# Projeto_Lora.net
KiCad netlist of a schematic drawn in EAGLE
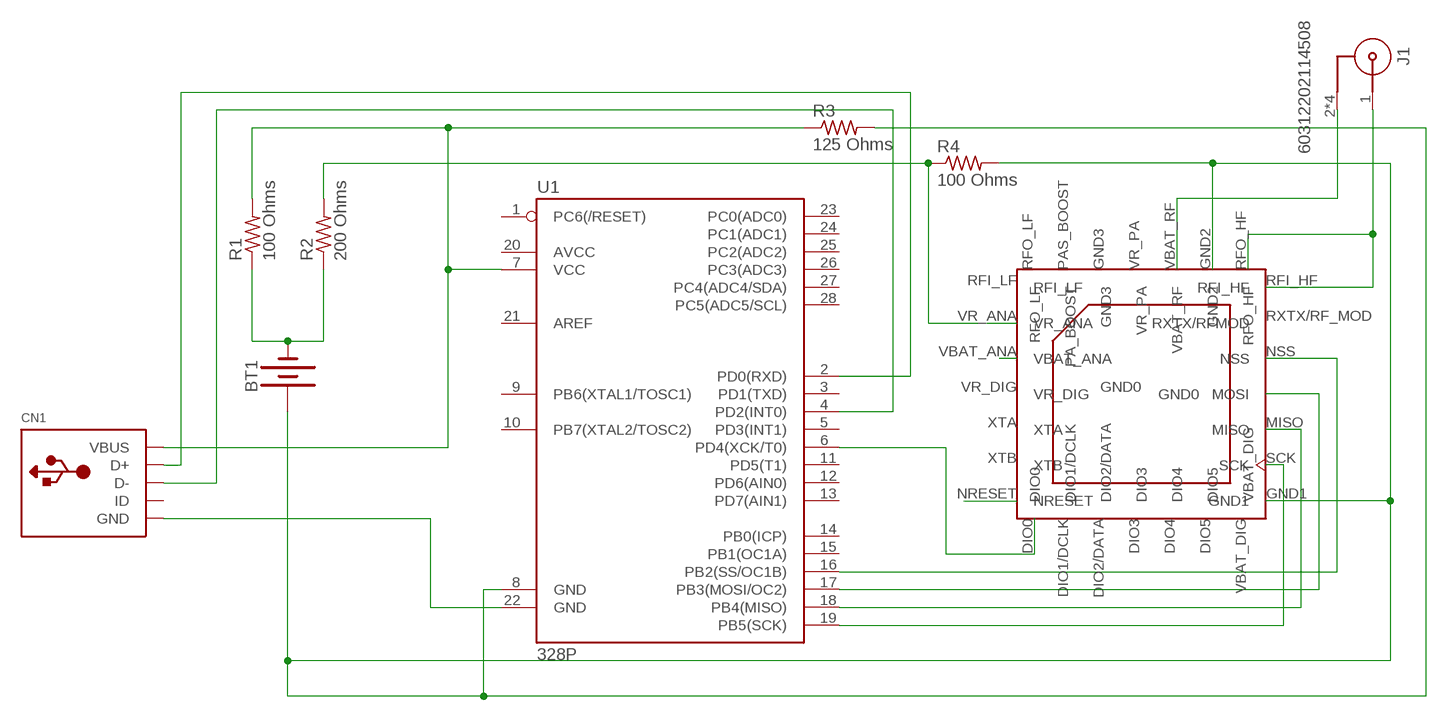
[diagram p0: schematic, sheet 1]

(export (version "E")
  (design (tool "Eeschema 10.0.6"))
  (components
    (comp (ref "BT1")
      (value "BATTERY-9V")
      (footprint "eagle-import:BATTCON_9V")
      (libsource (lib "eagle-import") (part "BATTERY-9V"))
    )
    (comp (ref "CN1")
      (value "USBMINIB")
      (footprint "eagle-import:USB-MINIB")
      (libsource (lib "eagle-import") (part "USBMINIB"))
    )
    (comp (ref "J1")
      (value "60312202114508")
      (footprint "eagle-import:60312202114508")
      (fields (field (name "MF") "Würth Elektronik") (field (name "MP") "SMA Connector"))
      (libsource (lib "eagle-import") (part "60312202114508"))
    )
    (comp (ref "R1")
      (value "100 Ohms")
      (footprint "eagle-import:R01005")
      (libsource (lib "eagle-import") (part "R-US_01005"))
    )
    (comp (ref "R2")
      (value "200 Ohms")
      (footprint "eagle-import:R01005")
      (libsource (lib "eagle-import") (part "R-US_01005"))
    )
    (comp (ref "R3")
      (value "125 Ohms")
      (footprint "eagle-import:R01005")
      (libsource (lib "eagle-import") (part "R-US_01005"))
    )
    (comp (ref "R4")
      (value "100 Ohms")
      (footprint "eagle-import:R01005")
      (libsource (lib "eagle-import") (part "R-US_01005"))
    )
    (comp (ref "U$1")
      (value "LORA-SX1278")
      (footprint "eagle-import:PDIP")
      (libsource (lib "eagle-import") (part "LORA-SX1278"))
    )
    (comp (ref "U1")
      (value "328P")
      (footprint "eagle-import:DIP28")
      (libsource (lib "eagle-import") (part "ATMEGA328P_PDIP"))
    )
  )
  (nets
    (net (code "1") (name "/GND0") (class "Default")
      (node (ref "U$1") (pin "GND0") (pinfunction "GND0_GND0") (pintype "power_in"))
    )
    (net (code "2") (name "/GND3") (class "Default")
      (node (ref "U$1") (pin "GND3") (pinfunction "GND3_GND3") (pintype "power_in"))
    )
    (net (code "3") (name "/VBAT_DIG") (class "Default")
      (node (ref "U$1") (pin "VBAT_DIG") (pinfunction "VBAT_DIG_VBAT_DIG") (pintype "power_in"))
    )
    (net (code "4") (name "/VR_DIG") (class "Default")
      (node (ref "U$1") (pin "VR_DIG") (pinfunction "VR_DIG_VR_DIG") (pintype "power_in"))
    )
    (net (code "5") (name "/VR_PA") (class "Default")
      (node (ref "U$1") (pin "VR_PA") (pinfunction "VR_PA_VR_PA") (pintype "power_in"))
    )
    (net (code "6") (name "Net-(BT1-Pad+)") (class "Default")
      (node (ref "BT1") (pin "+") (pinfunction "+_+") (pintype "power_in"))
      (node (ref "R3") (pin "2") (pinfunction "2_2") (pintype "passive"))
      (node (ref "R4") (pin "2") (pinfunction "2_2") (pintype "passive"))
      (node (ref "U$1") (pin "GND1") (pinfunction "GND1_GND1") (pintype "power_in"))
      (node (ref "U$1") (pin "GND2") (pinfunction "GND2_GND2") (pintype "power_in"))
      (node (ref "U1") (pin "8") (pinfunction "GND_8") (pintype "bidirectional"))
    )
    (net (code "7") (name "Net-(BT1-Pad-)") (class "Default")
      (node (ref "BT1") (pin "-") (pinfunction "-_-") (pintype "power_in"))
      (node (ref "R1") (pin "1") (pinfunction "1_1") (pintype "passive"))
      (node (ref "R2") (pin "1") (pinfunction "1_1") (pintype "passive"))
    )
    (net (code "8") (name "Net-(CN1-PadGND)") (class "Default")
      (node (ref "CN1") (pin "GND") (pinfunction "GND_GND") (pintype "power_in"))
      (node (ref "U1") (pin "22") (pinfunction "GND_22") (pintype "bidirectional"))
    )
    (net (code "9") (name "Net-(J1-2-Pad3)") (class "Default")
      (node (ref "J1") (pin "2") (pinfunction "2_2") (pintype "passive"))
      (node (ref "J1") (pin "3") (pinfunction "2_3") (pintype "passive"))
      (node (ref "J1") (pin "4") (pinfunction "2_4") (pintype "passive"))
      (node (ref "J1") (pin "5") (pinfunction "2_5") (pintype "passive"))
      (node (ref "U$1") (pin "VBAT_RF") (pinfunction "VBAT_RF_VBAT_RF") (pintype "power_in"))
    )
    (net (code "10") (name "Net-(J1-Pad1)") (class "Default")
      (node (ref "J1") (pin "1") (pinfunction "1_1") (pintype "passive"))
      (node (ref "U$1") (pin "RFI_HF") (pinfunction "RFI_HF_RFI_HF") (pintype "power_in"))
      (node (ref "U$1") (pin "RFO_HF") (pinfunction "RFO_HF_RFO_HF") (pintype "power_in"))
    )
    (net (code "11") (name "Net-(R2-Pad2)") (class "Default")
      (node (ref "R2") (pin "2") (pinfunction "2_2") (pintype "passive"))
      (node (ref "R4") (pin "1") (pinfunction "1_1") (pintype "passive"))
      (node (ref "U$1") (pin "VR_ANA") (pinfunction "VR_ANA_VR_ANA") (pintype "power_in"))
    )
    (net (code "12") (name "Net-(U1-PB2(SS{slash}OC1B))") (class "Default")
      (node (ref "U$1") (pin "NSS") (pinfunction "NSS_NSS") (pintype "input"))
      (node (ref "U1") (pin "16") (pinfunction "PB2(SS/OC1B)_16") (pintype "bidirectional"))
    )
    (net (code "13") (name "Net-(U1-PB3(MOSI{slash}OC2))") (class "Default")
      (node (ref "U$1") (pin "MOSI") (pinfunction "MOSI_MOSI") (pintype "input"))
      (node (ref "U1") (pin "17") (pinfunction "PB3(MOSI/OC2)_17") (pintype "bidirectional"))
    )
    (net (code "14") (name "Net-(U1-PB4(MISO))") (class "Default")
      (node (ref "U$1") (pin "MISO") (pinfunction "MISO_MISO") (pintype "output"))
      (node (ref "U1") (pin "18") (pinfunction "PB4(MISO)_18") (pintype "bidirectional"))
    )
    (net (code "15") (name "Net-(U1-PB5(SCK))") (class "Default")
      (node (ref "U$1") (pin "SCK") (pinfunction "SCK_SCK") (pintype "input"))
      (node (ref "U1") (pin "19") (pinfunction "PB5(SCK)_19") (pintype "bidirectional"))
    )
    (net (code "16") (name "Net-(U1-PD0(RXD))") (class "Default")
      (node (ref "CN1") (pin "D+") (pinfunction "D+_D+") (pintype "bidirectional"))
      (node (ref "U1") (pin "2") (pinfunction "PD0(RXD)_2") (pintype "bidirectional"))
    )
    (net (code "17") (name "Net-(U1-PD2(INT0))") (class "Default")
      (node (ref "CN1") (pin "D-") (pinfunction "D-_D-") (pintype "bidirectional"))
      (node (ref "U1") (pin "4") (pinfunction "PD2(INT0)_4") (pintype "bidirectional"))
    )
    (net (code "18") (name "Net-(U1-PD4(XCK{slash}T0))") (class "Default")
      (node (ref "U$1") (pin "DIO0") (pinfunction "DIO0_DIO0") (pintype "bidirectional"))
      (node (ref "U1") (pin "6") (pinfunction "PD4(XCK/T0)_6") (pintype "bidirectional"))
    )
    (net (code "19") (name "Net-(U1-VCC)") (class "Default")
      (node (ref "CN1") (pin "VBUS") (pinfunction "VBUS_VBUS") (pintype "power_in"))
      (node (ref "R1") (pin "2") (pinfunction "2_2") (pintype "passive"))
      (node (ref "R3") (pin "1") (pinfunction "1_1") (pintype "passive"))
      (node (ref "U1") (pin "7") (pinfunction "VCC_7") (pintype "bidirectional"))
    )
    (net (code "20") (name "unconnected-(CN1-PadID)") (class "Default")
      (node (ref "CN1") (pin "ID") (pinfunction "ID_ID") (pintype "bidirectional"))
    )
    (net (code "21") (name "unconnected-(U$1-PA_BOOST-PadPAS_BOOST)") (class "Default")
      (node (ref "U$1") (pin "PAS_BOOST") (pinfunction "PA_BOOST_PAS_BOOST") (pintype "output"))
    )
    (net (code "22") (name "unconnected-(U$1-PadDIO1{slash}DCLK)") (class "Default")
      (node (ref "U$1") (pin "DIO1/DCLK") (pinfunction "DIO1/DCLK_DIO1/DCLK") (pintype "bidirectional"))
    )
    (net (code "23") (name "unconnected-(U$1-PadDIO2{slash}DATA)") (class "Default")
      (node (ref "U$1") (pin "DIO2/DATA") (pinfunction "DIO2/DATA_DIO2/DATA") (pintype "bidirectional"))
    )
    (net (code "24") (name "unconnected-(U$1-PadDIO3)") (class "Default")
      (node (ref "U$1") (pin "DIO3") (pinfunction "DIO3_DIO3") (pintype "bidirectional"))
    )
    (net (code "25") (name "unconnected-(U$1-PadDIO4)") (class "Default")
      (node (ref "U$1") (pin "DIO4") (pinfunction "DIO4_DIO4") (pintype "bidirectional"))
    )
    (net (code "26") (name "unconnected-(U$1-PadDIO5)") (class "Default")
      (node (ref "U$1") (pin "DIO5") (pinfunction "DIO5_DIO5") (pintype "bidirectional"))
    )
    (net (code "27") (name "unconnected-(U$1-PadNRESET)") (class "Default")
      (node (ref "U$1") (pin "NRESET") (pinfunction "NRESET_NRESET") (pintype "bidirectional"))
    )
    (net (code "28") (name "unconnected-(U$1-PadRFI_LF)") (class "Default")
      (node (ref "U$1") (pin "RFI_LF") (pinfunction "RFI_LF_RFI_LF") (pintype "input"))
    )
    (net (code "29") (name "unconnected-(U$1-PadRFO_LF)") (class "Default")
      (node (ref "U$1") (pin "RFO_LF") (pinfunction "RFO_LF_RFO_LF") (pintype "output"))
    )
    (net (code "30") (name "unconnected-(U$1-PadVBAT_ANA)") (class "Default")
      (node (ref "U$1") (pin "VBAT_ANA") (pinfunction "VBAT_ANA_VBAT_ANA") (pintype "power_in"))
    )
    (net (code "31") (name "unconnected-(U$1-PadXTA)") (class "Default")
      (node (ref "U$1") (pin "XTA") (pinfunction "XTA_XTA") (pintype "bidirectional"))
    )
    (net (code "32") (name "unconnected-(U$1-PadXTB)") (class "Default")
      (node (ref "U$1") (pin "XTB") (pinfunction "XTB_XTB") (pintype "bidirectional"))
    )
    (net (code "33") (name "unconnected-(U$1-RXTX{slash}RFMOD-PadRXTX{slash}RF_MOD)") (class "Default")
      (node (ref "U$1") (pin "RXTX/RF_MOD") (pinfunction "RXTX/RFMOD_RXTX/RF_MOD") (pintype "output"))
    )
    (net (code "34") (name "unconnected-(U1-AREF-Pad21)") (class "Default")
      (node (ref "U1") (pin "21") (pinfunction "AREF_21") (pintype "bidirectional"))
    )
    (net (code "35") (name "unconnected-(U1-AVCC-Pad20)") (class "Default")
      (node (ref "U1") (pin "20") (pinfunction "AVCC_20") (pintype "bidirectional"))
    )
    (net (code "36") (name "unconnected-(U1-PB0(ICP)-Pad14)") (class "Default")
      (node (ref "U1") (pin "14") (pinfunction "PB0(ICP)_14") (pintype "bidirectional"))
    )
    (net (code "37") (name "unconnected-(U1-PB1(OC1A)-Pad15)") (class "Default")
      (node (ref "U1") (pin "15") (pinfunction "PB1(OC1A)_15") (pintype "bidirectional"))
    )
    (net (code "38") (name "unconnected-(U1-PB6(XTAL1{slash}TOSC1)-Pad9)") (class "Default")
      (node (ref "U1") (pin "9") (pinfunction "PB6(XTAL1/TOSC1)_9") (pintype "bidirectional"))
    )
    (net (code "39") (name "unconnected-(U1-PB7(XTAL2{slash}TOSC2)-Pad10)") (class "Default")
      (node (ref "U1") (pin "10") (pinfunction "PB7(XTAL2/TOSC2)_10") (pintype "bidirectional"))
    )
    (net (code "40") (name "unconnected-(U1-PC0(ADC0)-Pad23)") (class "Default")
      (node (ref "U1") (pin "23") (pinfunction "PC0(ADC0)_23") (pintype "bidirectional"))
    )
    (net (code "41") (name "unconnected-(U1-PC1(ADC1)-Pad24)") (class "Default")
      (node (ref "U1") (pin "24") (pinfunction "PC1(ADC1)_24") (pintype "bidirectional"))
    )
    (net (code "42") (name "unconnected-(U1-PC2(ADC2)-Pad25)") (class "Default")
      (node (ref "U1") (pin "25") (pinfunction "PC2(ADC2)_25") (pintype "bidirectional"))
    )
    (net (code "43") (name "unconnected-(U1-PC3(ADC3)-Pad26)") (class "Default")
      (node (ref "U1") (pin "26") (pinfunction "PC3(ADC3)_26") (pintype "bidirectional"))
    )
    (net (code "44") (name "unconnected-(U1-PC4(ADC4{slash}SDA)-Pad27)") (class "Default")
      (node (ref "U1") (pin "27") (pinfunction "PC4(ADC4/SDA)_27") (pintype "bidirectional"))
    )
    (net (code "45") (name "unconnected-(U1-PC5(ADC5{slash}SCL)-Pad28)") (class "Default")
      (node (ref "U1") (pin "28") (pinfunction "PC5(ADC5/SCL)_28") (pintype "bidirectional"))
    )
    (net (code "46") (name "unconnected-(U1-PC6({slash}RESET)-Pad1)") (class "Default")
      (node (ref "U1") (pin "1") (pinfunction "PC6(/RESET)_1") (pintype "bidirectional"))
    )
    (net (code "47") (name "unconnected-(U1-PD1(TXD)-Pad3)") (class "Default")
      (node (ref "U1") (pin "3") (pinfunction "PD1(TXD)_3") (pintype "bidirectional"))
    )
    (net (code "48") (name "unconnected-(U1-PD3(INT1)-Pad5)") (class "Default")
      (node (ref "U1") (pin "5") (pinfunction "PD3(INT1)_5") (pintype "bidirectional"))
    )
    (net (code "49") (name "unconnected-(U1-PD5(T1)-Pad11)") (class "Default")
      (node (ref "U1") (pin "11") (pinfunction "PD5(T1)_11") (pintype "bidirectional"))
    )
    (net (code "50") (name "unconnected-(U1-PD6(AIN0)-Pad12)") (class "Default")
      (node (ref "U1") (pin "12") (pinfunction "PD6(AIN0)_12") (pintype "bidirectional"))
    )
    (net (code "51") (name "unconnected-(U1-PD7(AIN1)-Pad13)") (class "Default")
      (node (ref "U1") (pin "13") (pinfunction "PD7(AIN1)_13") (pintype "bidirectional"))
    )
  )
)
